# 01-Insence_Power.net
KiCad netlist of a schematic drawn in Altium Designer
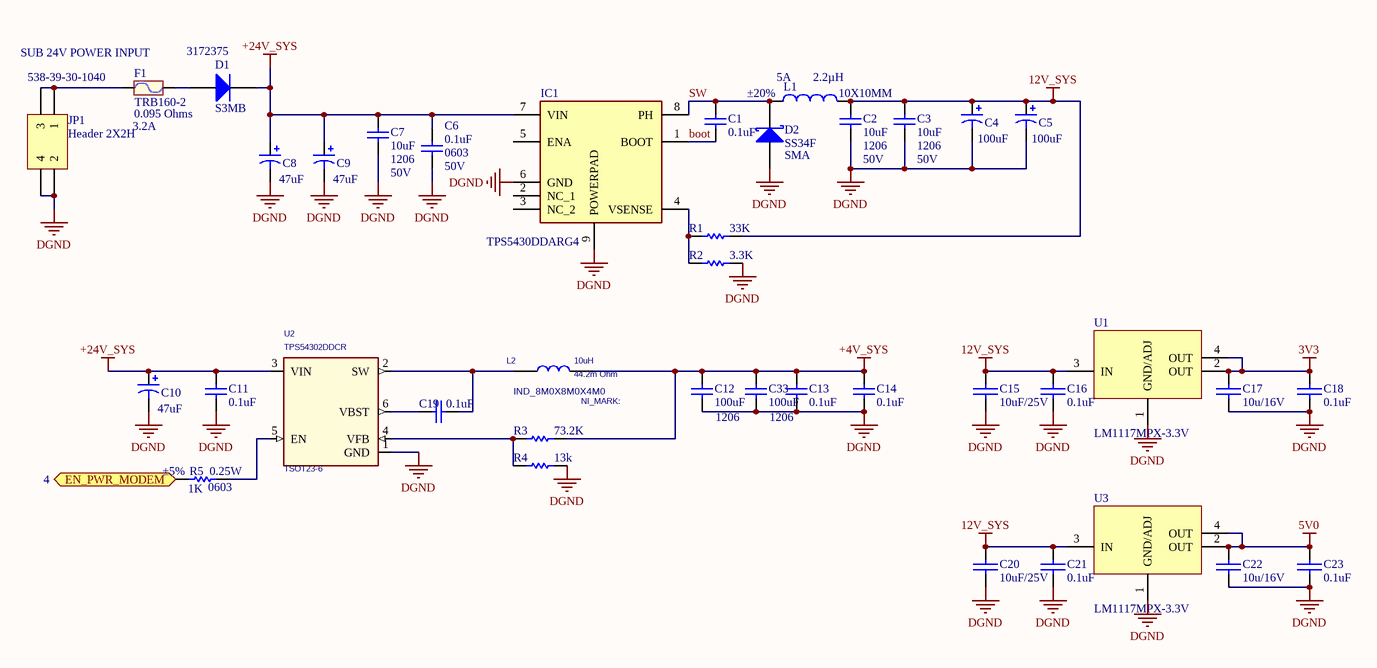
[diagram p0: 01-Insence_Power.SchDoc]

(export (version "E")
  (design (tool "Eeschema 10.0.6"))
  (components
    (comp (ref "C1")
      (value "Cap")
      (footprint "0805")
      (description "CAP CER 0.1UF 50V X7R 0805")
      (fields
        (field (name "=VALUE") "0.1uF")
        (field (name "MANUFACTURER1_PART#") "GMC21X7R104M50NT")
        (field (name "PUBLISHER") "Altium Limited")
      )
      (libsource (lib "Miscellaneous Devices") (part "Cap"))
    )
    (comp (ref "C2")
      (value "10uF")
      (footprint "1206")
      (description "CAP CER 10UF 50V X5R 1206")
      (fields
        (field (name "VOLTAGE") "50V")
        (field (name "TOLERANCE") "±10%")
        (field (name "MANUFACTURER1_PART#") "CL31A106MBHNNNE")
      )
      (libsource (lib "Slider") (part "Cap"))
    )
    (comp (ref "C3")
      (value "10uF")
      (footprint "1206")
      (description "CAP CER 10UF 50V X5R 1206")
      (fields
        (field (name "VOLTAGE") "50V")
        (field (name "TOLERANCE") "±10%")
        (field (name "MANUFACTURER1_PART#") "CL31A106MBHNNNE")
      )
      (libsource (lib "Slider") (part "Cap"))
    )
    (comp (ref "C4")
      (value "100uF")
      (footprint "CAP ALUM SMD-D Package 6.3x5.4mm")
      (description "CAP ALUM 100UF 20% 16V SMD")
      (fields
        (field (name "MANUFACTURER1_PART#") "UWX1C101MCL1GB")
        (field (name "MANUFACTURER2_PART#") "EDK107M016A9GAA")
      )
      (libsource (lib "My Library") (part "Cap TANTAN 100UF35V2917_1"))
    )
    (comp (ref "C5")
      (value "100uF")
      (footprint "CAP ALUM SMD-D Package 6.3x5.4mm")
      (description "CAP ALUM 100UF 20% 16V SMD")
      (fields
        (field (name "MANUFACTURER1_PART#") "UWX1C101MCL1GB")
        (field (name "MANUFACTURER2_PART#") "EDK107M016A9GAA")
      )
      (libsource (lib "My Library") (part "Cap TANTAN 100UF35V2917_1"))
    )
    (comp (ref "C6")
      (value "0.1uF")
      (footprint "0603")
      (description "CAP-CER,SMD;0.1UF,10%,50V,X7R,0603")
      (fields
        (field (name "VOLTAGE") "50V")
        (field (name "TOLERANCE") "±10%")
        (field (name "MANUFACTURER1_PART#") "CL10B104KB8NNNC")
      )
      (libsource (lib "Slider") (part "Cap"))
    )
    (comp (ref "C7")
      (value "10uF")
      (footprint "1206")
      (description "CAP CER 10UF 50V X5R 1206")
      (fields
        (field (name "VOLTAGE") "50V")
        (field (name "TOLERANCE") "±10%")
        (field (name "MANUFACTURER1_PART#") "CL31A106MBHNNNE")
      )
      (libsource (lib "Slider") (part "Cap"))
    )
    (comp (ref "C8")
      (value "47uF")
      (footprint "CAP ALUM SMD-D Package 6.3x5.4mm")
      (description "CAP ALUM 47UF 20% 35V SMD")
      (fields
        (field (name "MANUFACTURER1_PART#") "UUR1V470MCL6GS")
        (field (name "MANUFACTURER2_PART#") "EDK476M035A9GAA")
      )
      (libsource (lib "My Library") (part "Cap TANTAN 47UF35V2917"))
    )
    (comp (ref "C9")
      (value "47uF")
      (footprint "CAP ALUM SMD-D Package 6.3x5.4mm")
      (description "CAP ALUM 47UF 20% 35V SMD")
      (fields
        (field (name "MANUFACTURER1_PART#") "UUR1V470MCL6GS")
        (field (name "MANUFACTURER2_PART#") "EDK476M035A9GAA")
      )
      (libsource (lib "My Library") (part "Cap TANTAN 47UF35V2917"))
    )
    (comp (ref "C10")
      (value "47uF")
      (footprint "CAP ALUM SMD-D Package 6.3x5.4mm")
      (description "CAP ALUM 47UF 20% 35V SMD")
      (fields
        (field (name "MANUFACTURER1_PART#") "UUR1V470MCL6GS")
        (field (name "MANUFACTURER2_PART#") "EDK476M035A9GAA")
      )
      (libsource (lib "My Library") (part "Cap TANTAN 47UF35V2917"))
    )
    (comp (ref "C11")
      (value "Cap")
      (footprint "0805")
      (description "CAP CER 0.1UF 50V X7R 0805")
      (fields
        (field (name "=VALUE") "0.1uF")
        (field (name "MANUFACTURER1_PART#") "GMC21X7R104M50NT")
        (field (name "PUBLISHER") "Altium Limited")
      )
      (libsource (lib "Miscellaneous Devices") (part "Cap"))
    )
    (comp (ref "C12")
      (value "100uF")
      (footprint "CAP 1206")
      (description "CAP CER 100UF 6.3V X5R 1206")
      (fields
        (field (name "VOLTAGE") "6.3V")
        (field (name "PCB FOOTPRINT") "1206")
        (field (name "TOLERANCE") "±10%")
      )
      (libsource (lib "Slider") (part "Cap"))
    )
    (comp (ref "C13")
      (value "Cap")
      (footprint "0805")
      (description "CAP CER 0.1UF 50V X7R 0805")
      (fields
        (field (name "=VALUE") "0.1uF")
        (field (name "MANUFACTURER1_PART#") "GMC21X7R104M50NT")
        (field (name "PUBLISHER") "Altium Limited")
      )
      (libsource (lib "Miscellaneous Devices") (part "Cap"))
    )
    (comp (ref "C14")
      (value "Cap")
      (footprint "0805")
      (description "CAP CER 0.1UF 50V X7R 0805")
      (fields
        (field (name "=VALUE") "0.1uF")
        (field (name "MANUFACTURER1_PART#") "GMC21X7R104M50NT")
        (field (name "PUBLISHER") "Altium Limited")
      )
      (libsource (lib "Miscellaneous Devices") (part "Cap"))
    )
    (comp (ref "C15")
      (value "10uF/25V")
      (footprint "0805")
      (description "CAP CER 10UF 25V X5R 0805")
      (fields (field (name "MANUFACTURER1_PART#") "GMC21X5R106M25NT"))
      (libsource (lib "minhpv_sch") (part "CAP"))
    )
    (comp (ref "C16")
      (value "0.1uF")
      (footprint "0805")
      (description "CAP CER 0.1UF 50V X7R 0805")
      (fields (field (name "MANUFACTURER1_PART#") "GMC21X7R104M50NT"))
      (libsource (lib "minhpv_sch") (part "CAP"))
    )
    (comp (ref "C17")
      (value "10u/16V")
      (footprint "0805")
      (description "CAP CER 10UF 16V X5R 0805")
      (fields (field (name "MANUFACTURER1_PART#") "GMC21X5R106K16NT"))
      (libsource (lib "minhpv_sch") (part "CAP"))
    )
    (comp (ref "C18")
      (value "0.1uF")
      (footprint "0805")
      (description "CAP CER 0.1UF 50V X7R 0805")
      (fields (field (name "MANUFACTURER1_PART#") "GMC21X7R104M50NT"))
      (libsource (lib "minhpv_sch") (part "CAP"))
    )
    (comp (ref "C19")
      (value "Cap")
      (footprint "CAP 0603")
      (description "CAP CER 0.1UF 50V X5R 0603")
      (fields
        (field (name "=VALUE") "0.1uF")
        (field (name "MANUFACTURER1_PART#") "GMC10X5R104M50NT")
        (field (name "PUBLISHER") "Altium Limited")
      )
      (libsource (lib "Miscellaneous Devices") (part "Cap"))
    )
    (comp (ref "C20")
      (value "10uF/25V")
      (footprint "0805")
      (description "CAP CER 10UF 25V X5R 0805")
      (fields (field (name "MANUFACTURER1_PART#") "GMC21X5R106M25NT"))
      (libsource (lib "minhpv_sch") (part "CAP"))
    )
    (comp (ref "C21")
      (value "0.1uF")
      (footprint "0805")
      (description "CAP CER 0.1UF 50V X7R 0805")
      (fields (field (name "MANUFACTURER1_PART#") "GMC21X7R104M50NT"))
      (libsource (lib "minhpv_sch") (part "CAP"))
    )
    (comp (ref "C22")
      (value "10u/16V")
      (footprint "0805")
      (description "CAP CER 10UF 16V X5R 0805")
      (fields (field (name "MANUFACTURER1_PART#") "GMC21X5R106K16NT"))
      (libsource (lib "minhpv_sch") (part "CAP"))
    )
    (comp (ref "C23")
      (value "0.1uF")
      (footprint "0805")
      (description "CAP CER 0.1UF 50V X7R 0805")
      (fields (field (name "MANUFACTURER1_PART#") "GMC21X7R104M50NT"))
      (libsource (lib "minhpv_sch") (part "CAP"))
    )
    (comp (ref "C33")
      (value "100uF")
      (footprint "CAP 1206")
      (description "CAP CER 100UF 6.3V X5R 1206")
      (fields
        (field (name "VOLTAGE") "6.3V")
        (field (name "PCB FOOTPRINT") "1206")
        (field (name "TOLERANCE") "±10%")
      )
      (libsource (lib "Slider") (part "Cap"))
    )
    (comp (ref "D1")
      (value "S3MB")
      (footprint "DO-214AB")
      (description "Default Diode")
      (fields
        (field (name "MANUFACTURER1_PART#") "S3MB-13-F")
        (field (name "SUPPLIER PART NUMBER 1") "3172375")
        (field (name "PUBLISHER") "Altium Limited")
      )
      (libsource (lib "Miscellaneous Devices") (part "Diode"))
    )
    (comp (ref "D2")
      (value "SS34F")
      (footprint "SMA")
      (description "Diode 40 V 3A Surface Mount SMAF")
      (fields (field (name "PACKAGEREFERENCE") "SMA") (field (name "PUBLISHER") "Altium Limited"))
      (libsource (lib "Miscellaneous Devices") (part "D Schottky"))
    )
    (comp (ref "F1")
      (value "TRB160-2")
      (footprint "TRB160-2")
      (description "Polymeric 30V 3.2A 8s 95mO Through Hole,P=5.1mm,L=3.8mm PTC")
      (fields
        (field (name "MANUFACTURER2_PART#") "JK30-160")
        (field (name "DC COLD RESISTANCE") "0.095 Ohms")
        (field (name "CURRENT RATING (AMPS)") "3.2A")
      )
      (libsource (lib "K Shematic") (part "0875.800MXEP"))
    )
    (comp (ref "IC1")
      (value "TPS5430DDARG4")
      (footprint "Hiendv:SOIC127P600X170-9N")
      (description "Integrated Circuit")
      (fields (field (name "MOUSER PART NUMBER") "595-TPS5430DDARG4"))
      (libsource (lib "lib") (part "TPS5430DDARG4"))
    )
    (comp (ref "JP1")
      (value "Header 2X2H")
      (footprint "HDR2x2 4_2MM FEMALE TH RA")
      (description "CONN HEADER R/A 4POS 4.2MM")
      (fields
        (field (name "SUPPLIER PART NUMBER 1") "538-39-30-1040")
        (field (name "MANUFACTURER1_PART#") "0039301040")
        (field (name "PUBLISHER") "Altium Limited")
      )
      (libsource (lib "Miscellaneous Connectors") (part "Header 2X2H"))
    )
    (comp (ref "L1")
      (value "2.2µH")
      (footprint "IND 8x8MM")
      (description "FIXED IND 22UH 5A SMD 8x8mm")
      (fields
        (field (name "MANUFACTURER1_PART#") "SRP7050WA-220M")
        (field (name "PCB FOOTPRINT") "10X10MM")
        (field (name "RATE CURRENT") "5A")
        (field (name "TOLERANCE") "±20%")
      )
      (libsource (lib "Full") (part "inductor 2.2uF"))
    )
    (comp (ref "L2")
      (value "10uH")
      (footprint "IND 8x8MM")
      (description "IND-SMD;10uH,20%,8x8x4mm,3.1A,44.2mOHM")
      (fields
        (field (name "PACKAGE") "IND_8M0X8M0X4M0")
        (field (name "TOLERANCE") "20%")
        (field (name "MFG1_PART#") "NR8040T100M")
        (field (name "DCR") "44.2m Ohm")
        (field (name "BY") "VINFAST_RD")
      )
      (libsource (lib "*") (part "IND_10uH_3.1A_44.2mOhm_8MX8MX4M"))
    )
    (comp (ref "R1")
      (value "33K")
      (footprint "res 0603")
      (description "RES SMD 33K OHM 1% 1/10W 0603")
      (fields
        (field (name "MANUFACTURER1_PART#") "RM06F3302CT")
        (field (name "Comment") "Res1")
        (field (name "PUBLISHER") "Altium Limited")
      )
      (libsource (lib "Miscellaneous Devices") (part "Res1"))
    )
    (comp (ref "R2")
      (value "3.3K")
      (footprint "res 0603")
      (description "RES SMD 3.3K OHM 1% 1/10W 0603")
      (fields
        (field (name "MANUFACTURER1_PART#") "RM06F3301CT")
        (field (name "Comment") "Res1")
        (field (name "PUBLISHER") "Altium Limited")
      )
      (libsource (lib "Miscellaneous Devices") (part "Res1"))
    )
    (comp (ref "R3")
      (value "73.2K")
      (footprint "res 0603")
      (description "RES SMD 73.2K OHM 1% 1/10W 0603")
      (fields
        (field (name "MANUFACTURER1_PART#") "RM06F7322CT")
        (field (name "Comment") "Res1")
        (field (name "PUBLISHER") "Altium Limited")
      )
      (libsource (lib "Miscellaneous Devices") (part "Res1"))
    )
    (comp (ref "R4")
      (value "13k")
      (footprint "res 0603")
      (description "RES SMD 13K OHM 1% 1/10W 0603")
      (fields
        (field (name "MANUFACTURER1_PART#") "RM06F1302CT")
        (field (name "Comment") "Res1")
        (field (name "PUBLISHER") "Altium Limited")
      )
      (libsource (lib "Miscellaneous Devices") (part "Res1"))
    )
    (comp (ref "R5")
      (value "1K")
      (footprint "res 0603")
      (description "RES SMD,1K OHM,5%,1/10W,0603")
      (fields
        (field (name "MANUFACTURER1_PART#") "RMCF06031K00JNEAC")
        (field (name "MANUFACTURER2_PART#") "R0603J1KTG")
        (field (name "PCB FOOTPRINT") "0603")
        (field (name "POWER") "0.25W")
        (field (name "TOLERANCE") "±5%")
      )
      (libsource (lib "Full") (part "Res0.3"))
    )
    (comp (ref "U1")
      (value "LM1117MPX-3.3V")
      (footprint "SOT223")
      (description "LDO, LM1117MPX-3.3V")
      (libsource (lib "lib") (part "LM1117"))
    )
    (comp (ref "U2")
      (value "TPS54302DDCR")
      (footprint "SOT23-6")
      (description "IC REG BUCK ADJ 3A TSOT23-6,TPS54302DDCR")
      (fields
        (field (name "DISTR1_PART#") "296-46237-1-ND")
        (field (name "PACKAGE") "TSOT23-6")
        (field (name "BY") "VINFAST_RD")
      )
      (libsource (lib "*") (part "IC_TPS54302DDCR"))
    )
    (comp (ref "U3")
      (value "LM1117MPX-3.3V")
      (footprint "SOT223")
      (description "LDO, LM1117MPX-3.3V")
      (libsource (lib "lib") (part "LM1117"))
    )
  )
  (nets
    (net (code "1") (name "+4V_SYS") (class "Default")
      (node (ref "C12") (pin "1") (pinfunction "1_1") (pintype "passive"))
      (node (ref "C13") (pin "2") (pinfunction "2_2") (pintype "passive"))
      (node (ref "C14") (pin "2") (pinfunction "2_2") (pintype "passive"))
      (node (ref "C33") (pin "1") (pinfunction "1_1") (pintype "passive"))
      (node (ref "L2") (pin "2") (pinfunction "B_2") (pintype "passive"))
      (node (ref "R3") (pin "2") (pinfunction "2_2") (pintype "passive"))
    )
    (net (code "2") (name "+24V_SYS") (class "Default")
      (node (ref "C10") (pin "1") (pinfunction "1_1") (pintype "passive"))
      (node (ref "C11") (pin "2") (pinfunction "2_2") (pintype "passive"))
      (node (ref "C6") (pin "2") (pinfunction "2_2") (pintype "passive"))
      (node (ref "C7") (pin "2") (pinfunction "2_2") (pintype "passive"))
      (node (ref "C8") (pin "1") (pinfunction "1_1") (pintype "passive"))
      (node (ref "C9") (pin "1") (pinfunction "1_1") (pintype "passive"))
      (node (ref "D1") (pin "2") (pinfunction "K_2") (pintype "passive"))
      (node (ref "IC1") (pin "7") (pinfunction "VIN_7") (pintype "passive"))
      (node (ref "U2") (pin "3") (pinfunction "VIN_3") (pintype "power_in"))
    )
    (net (code "3") (name "/EN_PWR_MODEM") (class "Default")
      (node (ref "R5") (pin "2") (pinfunction "2_2") (pintype "passive"))
    )
    (net (code "4") (name "/SW") (class "Default")
      (node (ref "C1") (pin "2") (pinfunction "2_2") (pintype "passive"))
      (node (ref "D2") (pin "2") (pinfunction "K_2") (pintype "passive"))
      (node (ref "IC1") (pin "8") (pinfunction "PH_8") (pintype "passive"))
      (node (ref "L1") (pin "1") (pinfunction "1_1") (pintype "passive"))
    )
    (net (code "5") (name "/boot") (class "Default")
      (node (ref "C1") (pin "1") (pinfunction "1_1") (pintype "passive"))
      (node (ref "IC1") (pin "1") (pinfunction "BOOT_1") (pintype "passive"))
    )
    (net (code "6") (name "3V3") (class "Default")
      (node (ref "C17") (pin "1") (pinfunction "1_1") (pintype "passive"))
      (node (ref "C18") (pin "1") (pinfunction "1_1") (pintype "passive"))
      (node (ref "U1") (pin "2") (pinfunction "OUT_2") (pintype "passive"))
      (node (ref "U1") (pin "4") (pinfunction "OUT_4") (pintype "passive"))
    )
    (net (code "7") (name "5V0") (class "Default")
      (node (ref "C22") (pin "1") (pinfunction "1_1") (pintype "passive"))
      (node (ref "C23") (pin "1") (pinfunction "1_1") (pintype "passive"))
      (node (ref "U3") (pin "2") (pinfunction "OUT_2") (pintype "passive"))
      (node (ref "U3") (pin "4") (pinfunction "OUT_4") (pintype "passive"))
    )
    (net (code "8") (name "12V_SYS") (class "Default")
      (node (ref "C15") (pin "1") (pinfunction "1_1") (pintype "passive"))
      (node (ref "C16") (pin "1") (pinfunction "1_1") (pintype "passive"))
      (node (ref "C2") (pin "2") (pinfunction "2_2") (pintype "passive"))
      (node (ref "C20") (pin "1") (pinfunction "1_1") (pintype "passive"))
      (node (ref "C21") (pin "1") (pinfunction "1_1") (pintype "passive"))
      (node (ref "C3") (pin "2") (pinfunction "2_2") (pintype "passive"))
      (node (ref "C4") (pin "1") (pinfunction "1_1") (pintype "passive"))
      (node (ref "C5") (pin "1") (pinfunction "1_1") (pintype "passive"))
      (node (ref "L1") (pin "2") (pinfunction "2_2") (pintype "passive"))
      (node (ref "R1") (pin "2") (pinfunction "2_2") (pintype "passive"))
      (node (ref "U1") (pin "3") (pinfunction "IN_3") (pintype "passive"))
      (node (ref "U3") (pin "3") (pinfunction "IN_3") (pintype "passive"))
    )
    (net (code "9") (name "DGND") (class "Default")
      (node (ref "C10") (pin "2") (pinfunction "2_2") (pintype "passive"))
      (node (ref "C11") (pin "1") (pinfunction "1_1") (pintype "passive"))
      (node (ref "C12") (pin "2") (pinfunction "2_2") (pintype "passive"))
      (node (ref "C13") (pin "1") (pinfunction "1_1") (pintype "passive"))
      (node (ref "C14") (pin "1") (pinfunction "1_1") (pintype "passive"))
      (node (ref "C15") (pin "2") (pinfunction "2_2") (pintype "passive"))
      (node (ref "C16") (pin "2") (pinfunction "2_2") (pintype "passive"))
      (node (ref "C17") (pin "2") (pinfunction "2_2") (pintype "passive"))
      (node (ref "C18") (pin "2") (pinfunction "2_2") (pintype "passive"))
      (node (ref "C2") (pin "1") (pinfunction "1_1") (pintype "passive"))
      (node (ref "C20") (pin "2") (pinfunction "2_2") (pintype "passive"))
      (node (ref "C21") (pin "2") (pinfunction "2_2") (pintype "passive"))
      (node (ref "C22") (pin "2") (pinfunction "2_2") (pintype "passive"))
      (node (ref "C23") (pin "2") (pinfunction "2_2") (pintype "passive"))
      (node (ref "C3") (pin "1") (pinfunction "1_1") (pintype "passive"))
      (node (ref "C33") (pin "2") (pinfunction "2_2") (pintype "passive"))
      (node (ref "C4") (pin "2") (pinfunction "2_2") (pintype "passive"))
      (node (ref "C5") (pin "2") (pinfunction "2_2") (pintype "passive"))
      (node (ref "C6") (pin "1") (pinfunction "1_1") (pintype "passive"))
      (node (ref "C7") (pin "1") (pinfunction "1_1") (pintype "passive"))
      (node (ref "C8") (pin "2") (pinfunction "2_2") (pintype "passive"))
      (node (ref "C9") (pin "2") (pinfunction "2_2") (pintype "passive"))
      (node (ref "D2") (pin "1") (pinfunction "A_1") (pintype "passive"))
      (node (ref "IC1") (pin "6") (pinfunction "GND_6") (pintype "passive"))
      (node (ref "IC1") (pin "9") (pinfunction "POWERPAD_9") (pintype "passive"))
      (node (ref "JP1") (pin "2") (pinfunction "2_2") (pintype "passive"))
      (node (ref "JP1") (pin "4") (pinfunction "4_4") (pintype "passive"))
      (node (ref "R2") (pin "2") (pinfunction "2_2") (pintype "passive"))
      (node (ref "R4") (pin "2") (pinfunction "2_2") (pintype "passive"))
      (node (ref "U1") (pin "1") (pinfunction "GND/ADJ_1") (pintype "passive"))
      (node (ref "U2") (pin "1") (pinfunction "GND_1") (pintype "power_in"))
      (node (ref "U3") (pin "1") (pinfunction "GND/ADJ_1") (pintype "passive"))
    )
    (net (code "10") (name "Net-(D1-A)") (class "Default")
      (node (ref "D1") (pin "1") (pinfunction "A_1") (pintype "passive"))
      (node (ref "F1") (pin "2") (pinfunction "2_2") (pintype "passive"))
    )
    (net (code "11") (name "Net-(F1-Pad1)") (class "Default")
      (node (ref "F1") (pin "1") (pinfunction "1_1") (pintype "passive"))
      (node (ref "JP1") (pin "1") (pinfunction "1_1") (pintype "passive"))
      (node (ref "JP1") (pin "3") (pinfunction "3_3") (pintype "passive"))
    )
    (net (code "12") (name "Net-(IC1-VSENSE)") (class "Default")
      (node (ref "IC1") (pin "4") (pinfunction "VSENSE_4") (pintype "passive"))
      (node (ref "R1") (pin "1") (pinfunction "1_1") (pintype "passive"))
      (node (ref "R2") (pin "1") (pinfunction "1_1") (pintype "passive"))
    )
    (net (code "13") (name "Net-(L2-A)") (class "Default")
      (node (ref "C19") (pin "2") (pinfunction "2_2") (pintype "passive"))
      (node (ref "L2") (pin "1") (pinfunction "A_1") (pintype "passive"))
      (node (ref "U2") (pin "2") (pinfunction "SW_2") (pintype "output"))
    )
    (net (code "14") (name "Net-(U2-EN)") (class "Default")
      (node (ref "R5") (pin "1") (pinfunction "1_1") (pintype "passive"))
      (node (ref "U2") (pin "5") (pinfunction "EN_5") (pintype "input"))
    )
    (net (code "15") (name "Net-(U2-VBST)") (class "Default")
      (node (ref "C19") (pin "1") (pinfunction "1_1") (pintype "passive"))
      (node (ref "U2") (pin "6") (pinfunction "VBST_6") (pintype "output"))
    )
    (net (code "16") (name "Net-(U2-VFB)") (class "Default")
      (node (ref "R3") (pin "1") (pinfunction "1_1") (pintype "passive"))
      (node (ref "R4") (pin "1") (pinfunction "1_1") (pintype "passive"))
      (node (ref "U2") (pin "4") (pinfunction "VFB_4") (pintype "input"))
    )
    (net (code "17") (name "unconnected-(IC1-ENA-Pad5)") (class "Default")
      (node (ref "IC1") (pin "5") (pinfunction "ENA_5") (pintype "passive"))
    )
    (net (code "18") (name "unconnected-(IC1-NC_1-Pad2)") (class "Default")
      (node (ref "IC1") (pin "2") (pinfunction "NC_1_2") (pintype "passive"))
    )
    (net (code "19") (name "unconnected-(IC1-NC_2-Pad3)") (class "Default")
      (node (ref "IC1") (pin "3") (pinfunction "NC_2_3") (pintype "passive"))
    )
  )
)
